# P05_PVDF.net
KiCad netlist of a schematic drawn in EasyEDA
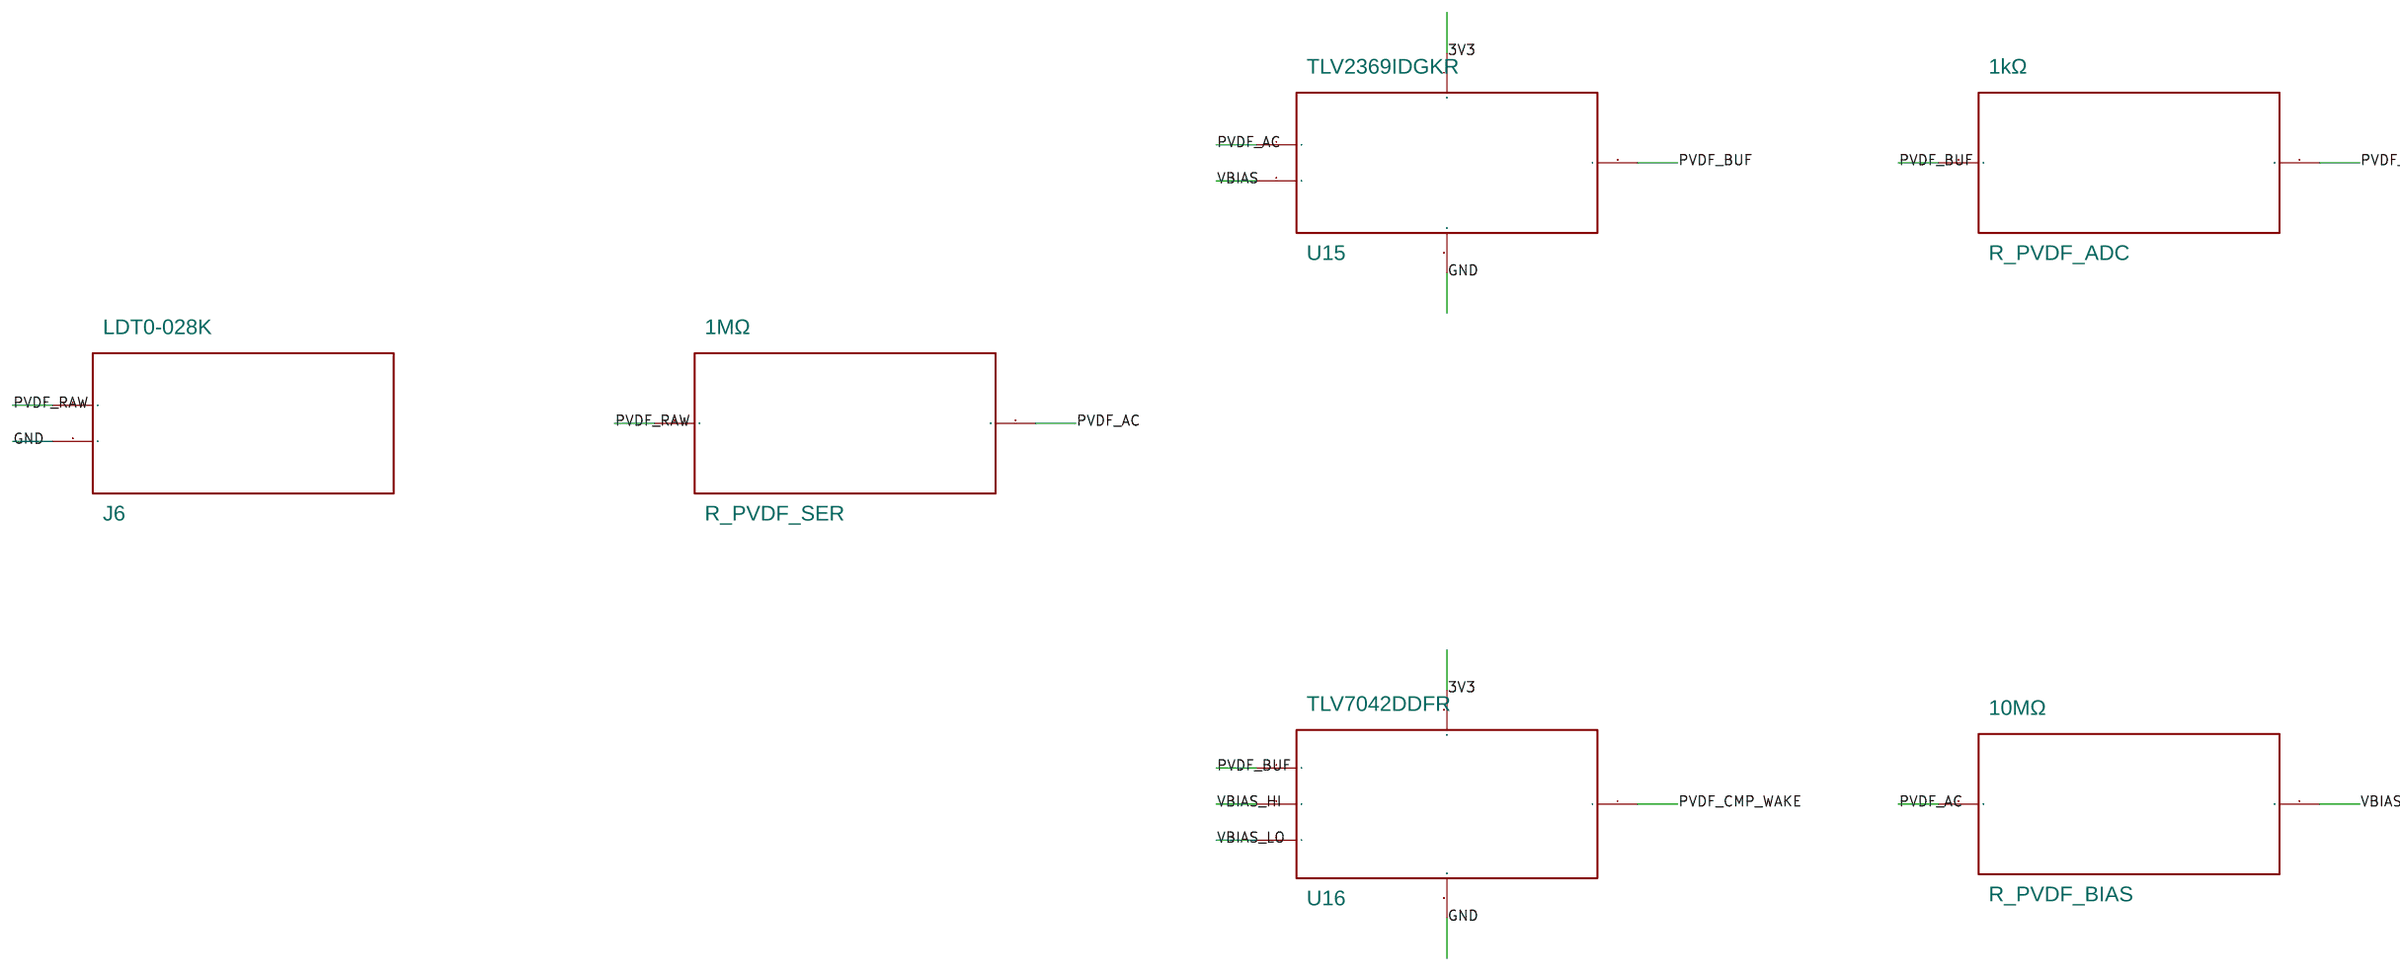
[diagram p0: schematic sheet]

(export (version "E")
  (design (tool "Eeschema 10.0.6"))
  (components
    (comp (ref "J6") (value "LDT0-028K") (libsource (lib "") (part "PVDF")))
    (comp (ref "R_PVDF_ADC") (value "1kΩ") (libsource (lib "") (part "Resistor")))
    (comp (ref "R_PVDF_BIAS") (value "10MΩ") (libsource (lib "") (part "Resistor_2")))
    (comp (ref "R_PVDF_SER") (value "1MΩ") (libsource (lib "") (part "Resistor_1")))
    (comp (ref "U15") (value "TLV2369IDGKR") (libsource (lib "") (part "OpAmp")))
    (comp (ref "U16") (value "TLV7042DDFR") (libsource (lib "") (part "Comparator")))
  )
  (nets
    (net (code "1") (name "/3V3") (class "Default")
      (node (ref "U15") (pin "4") (pinfunction "1_4") (pintype "unspecified"))
      (node (ref "U16") (pin "5") (pinfunction "1_5") (pintype "unspecified"))
    )
    (net (code "2") (name "/GND") (class "Default")
      (node (ref "J6") (pin "2") (pinfunction "1_2") (pintype "unspecified"))
      (node (ref "U15") (pin "5") (pinfunction "1_5") (pintype "unspecified"))
      (node (ref "U16") (pin "6") (pinfunction "1_6") (pintype "unspecified"))
    )
    (net (code "3") (name "/PVDF_AC") (class "Default")
      (node (ref "R_PVDF_BIAS") (pin "1") (pinfunction "1_1") (pintype "unspecified"))
      (node (ref "R_PVDF_SER") (pin "2") (pinfunction "1_2") (pintype "unspecified"))
      (node (ref "U15") (pin "1") (pinfunction "1_1") (pintype "unspecified"))
    )
    (net (code "4") (name "/PVDF_ADC") (class "Default")
      (node (ref "R_PVDF_ADC") (pin "2") (pinfunction "1_2") (pintype "unspecified"))
    )
    (net (code "5") (name "/PVDF_BUF") (class "Default")
      (node (ref "R_PVDF_ADC") (pin "1") (pinfunction "1_1") (pintype "unspecified"))
      (node (ref "U15") (pin "3") (pinfunction "1_3") (pintype "unspecified"))
      (node (ref "U16") (pin "1") (pinfunction "1_1") (pintype "unspecified"))
    )
    (net (code "6") (name "/PVDF_CMP_WAKE") (class "Default")
      (node (ref "U16") (pin "4") (pinfunction "1_4") (pintype "unspecified"))
    )
    (net (code "7") (name "/PVDF_RAW") (class "Default")
      (node (ref "J6") (pin "1") (pinfunction "1_1") (pintype "unspecified"))
      (node (ref "R_PVDF_SER") (pin "1") (pinfunction "1_1") (pintype "unspecified"))
    )
    (net (code "8") (name "/VBIAS") (class "Default")
      (node (ref "R_PVDF_BIAS") (pin "2") (pinfunction "1_2") (pintype "unspecified"))
      (node (ref "U15") (pin "2") (pinfunction "1_2") (pintype "unspecified"))
    )
    (net (code "9") (name "/VBIAS_HI") (class "Default")
      (node (ref "U16") (pin "2") (pinfunction "1_2") (pintype "unspecified"))
    )
    (net (code "10") (name "/VBIAS_LO") (class "Default")
      (node (ref "U16") (pin "3") (pinfunction "1_3") (pintype "unspecified"))
    )
  )
)
